# Blue_Pill_Clock.net
KiCad netlist of a schematic drawn in Altium Designer
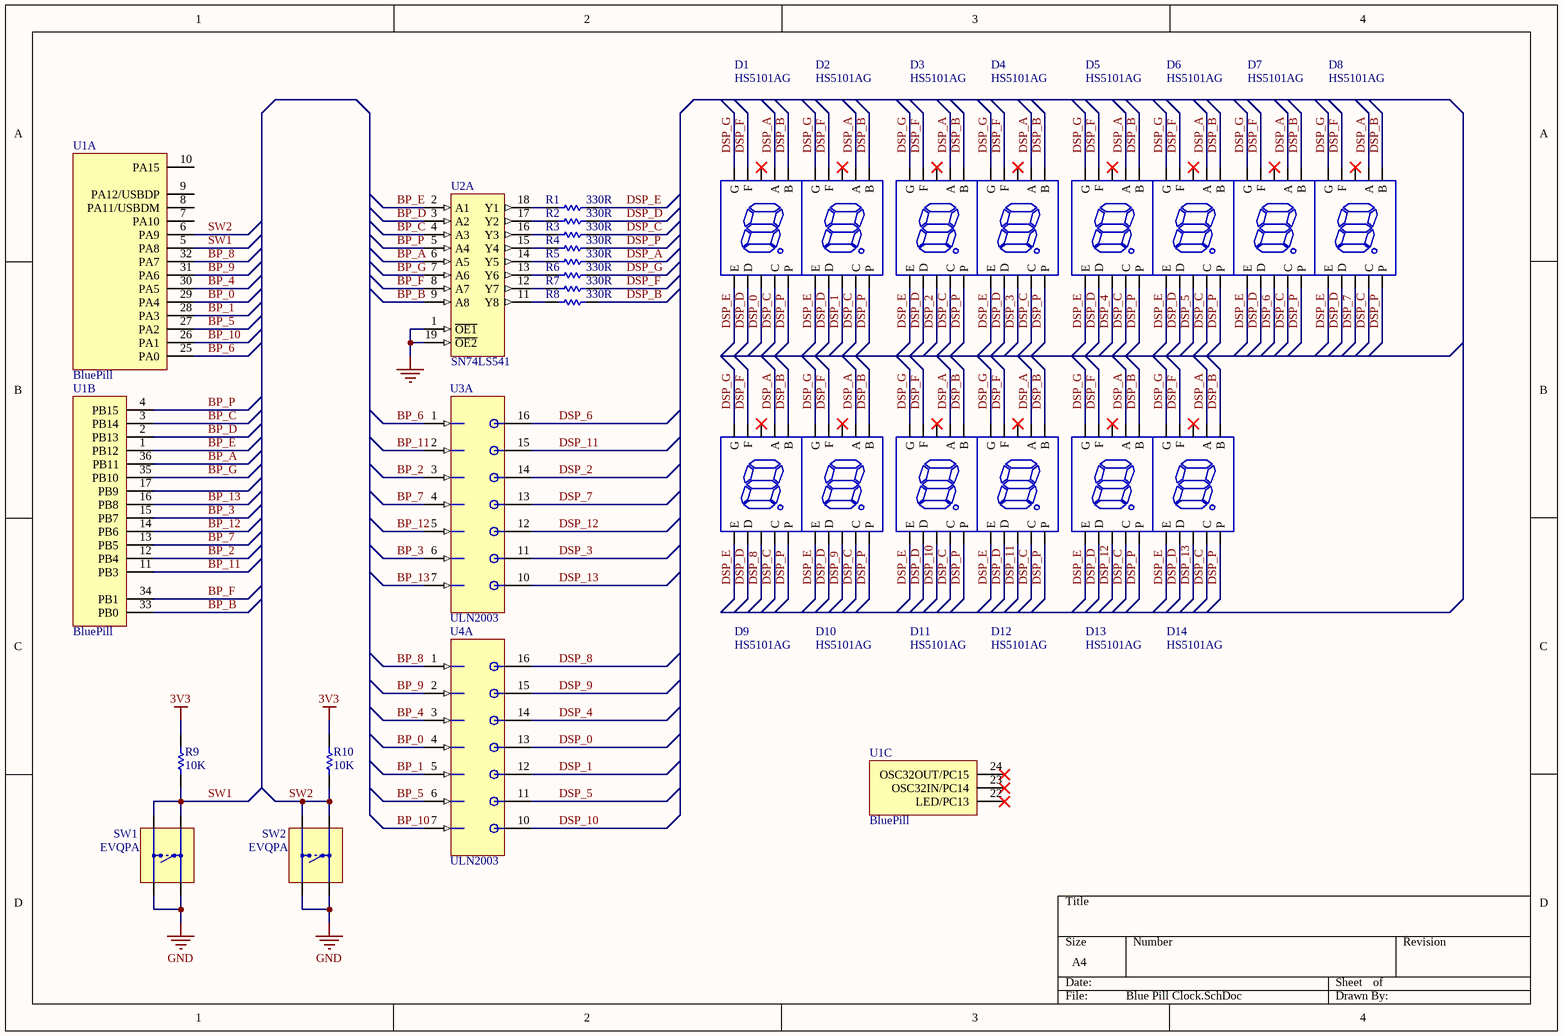
[diagram p0: Blue Pill Clock.SchDoc]

(export (version "E")
  (design (tool "Eeschema 10.0.6"))
  (components
    (comp (ref "D1")
      (value "HS5101AG")
      (footprint "HS5101AG")
      (description "Display 7-Segments Cathodo Common")
      (libsource (lib "Basic") (part "HS5101AG"))
    )
    (comp (ref "D2")
      (value "HS5101AG")
      (footprint "HS5101AG")
      (description "Display 7-Segments Cathodo Common")
      (libsource (lib "Basic") (part "HS5101AG"))
    )
    (comp (ref "D3")
      (value "HS5101AG")
      (footprint "HS5101AG")
      (description "Display 7-Segments Cathodo Common")
      (libsource (lib "Basic") (part "HS5101AG"))
    )
    (comp (ref "D4")
      (value "HS5101AG")
      (footprint "HS5101AG")
      (description "Display 7-Segments Cathodo Common")
      (libsource (lib "Basic") (part "HS5101AG"))
    )
    (comp (ref "D5")
      (value "HS5101AG")
      (footprint "HS5101AG")
      (description "Display 7-Segments Cathodo Common")
      (libsource (lib "Basic") (part "HS5101AG"))
    )
    (comp (ref "D6")
      (value "HS5101AG")
      (footprint "HS5101AG")
      (description "Display 7-Segments Cathodo Common")
      (libsource (lib "Basic") (part "HS5101AG"))
    )
    (comp (ref "D7")
      (value "HS5101AG")
      (footprint "HS5101AG")
      (description "Display 7-Segments Cathodo Common")
      (libsource (lib "Basic") (part "HS5101AG"))
    )
    (comp (ref "D8")
      (value "HS5101AG")
      (footprint "HS5101AG")
      (description "Display 7-Segments Cathodo Common")
      (libsource (lib "Basic") (part "HS5101AG"))
    )
    (comp (ref "D9")
      (value "HS5101AG")
      (footprint "HS5101AG")
      (description "Display 7-Segments Cathodo Common")
      (libsource (lib "Basic") (part "HS5101AG"))
    )
    (comp (ref "D10")
      (value "HS5101AG")
      (footprint "HS5101AG")
      (description "Display 7-Segments Cathodo Common")
      (libsource (lib "Basic") (part "HS5101AG"))
    )
    (comp (ref "D11")
      (value "HS5101AG")
      (footprint "HS5101AG")
      (description "Display 7-Segments Cathodo Common")
      (libsource (lib "Basic") (part "HS5101AG"))
    )
    (comp (ref "D12")
      (value "HS5101AG")
      (footprint "HS5101AG")
      (description "Display 7-Segments Cathodo Common")
      (libsource (lib "Basic") (part "HS5101AG"))
    )
    (comp (ref "D13")
      (value "HS5101AG")
      (footprint "HS5101AG")
      (description "Display 7-Segments Cathodo Common")
      (libsource (lib "Basic") (part "HS5101AG"))
    )
    (comp (ref "D14")
      (value "HS5101AG")
      (footprint "HS5101AG")
      (description "Display 7-Segments Cathodo Common")
      (libsource (lib "Basic") (part "HS5101AG"))
    )
    (comp (ref "R1")
      (value "330R")
      (footprint "0805")
      (description "Resistor")
      (libsource (lib "Basic") (part "Resistor"))
    )
    (comp (ref "R2")
      (value "330R")
      (footprint "0805")
      (description "Resistor")
      (libsource (lib "Basic") (part "Resistor"))
    )
    (comp (ref "R3")
      (value "330R")
      (footprint "0805")
      (description "Resistor")
      (libsource (lib "Basic") (part "Resistor"))
    )
    (comp (ref "R4")
      (value "330R")
      (footprint "0805")
      (description "Resistor")
      (libsource (lib "Basic") (part "Resistor"))
    )
    (comp (ref "R5")
      (value "330R")
      (footprint "0805")
      (description "Resistor")
      (libsource (lib "Basic") (part "Resistor"))
    )
    (comp (ref "R6")
      (value "330R")
      (footprint "0805")
      (description "Resistor")
      (libsource (lib "Basic") (part "Resistor"))
    )
    (comp (ref "R7")
      (value "330R")
      (footprint "0805")
      (description "Resistor")
      (libsource (lib "Basic") (part "Resistor"))
    )
    (comp (ref "R8")
      (value "330R")
      (footprint "0805")
      (description "Resistor")
      (libsource (lib "Basic") (part "Resistor"))
    )
    (comp (ref "R9")
      (value "10K")
      (footprint "0805")
      (description "Resistor")
      (libsource (lib "Basic") (part "Resistor"))
    )
    (comp (ref "R10")
      (value "10K")
      (footprint "0805")
      (description "Resistor")
      (libsource (lib "Basic") (part "Resistor"))
    )
    (comp (ref "SW1")
      (value "EVQPA")
      (footprint "EVQPAx09K")
      (description "5N Type Light Touch Switches")
      (libsource (lib "Panasonic") (part "EVQPA"))
    )
    (comp (ref "SW2")
      (value "EVQPA")
      (footprint "EVQPAx09K")
      (description "5N Type Light Touch Switches")
      (libsource (lib "Panasonic") (part "EVQPA"))
    )
    (comp (ref "U1")
      (value "BluePill")
      (footprint "Blue Pill")
      (description "STM32 Blue Pill")
      (libsource (lib "STM32 Blue Pill") (part "Blue Pill - Model 1"))
    )
    (comp (ref "U2")
      (value "SN74LS541")
      (footprint "PDIP20")
      (description "Octal Buffers and Line Drivers With 3-State Outputs")
      (libsource (lib "Texas Instruments") (part "SN74HC541 Type-2"))
    )
    (comp (ref "U3")
      (value "ULN2003")
      (footprint "PDIP16")
      (description "Seven Darlington arrays")
      (libsource (lib "ST Microelectronics") (part "UN200x - Model 1"))
    )
    (comp (ref "U4")
      (value "ULN2003")
      (footprint "PDIP16")
      (description "Seven Darlington arrays")
      (libsource (lib "ST Microelectronics") (part "UN200x - Model 1"))
    )
  )
  (nets
    (net (code "1") (name "/BP_0") (class "Default")
      (node (ref "U1") (pin "29") (pinfunction "PA4_29") (pintype "passive"))
      (node (ref "U4") (pin "4") (pinfunction "4_4") (pintype "input"))
    )
    (net (code "2") (name "/BP_1") (class "Default")
      (node (ref "U1") (pin "28") (pinfunction "PA3_28") (pintype "passive"))
      (node (ref "U4") (pin "5") (pinfunction "5_5") (pintype "input"))
    )
    (net (code "3") (name "/BP_2") (class "Default")
      (node (ref "U1") (pin "12") (pinfunction "PB4_12") (pintype "passive"))
      (node (ref "U3") (pin "3") (pinfunction "3_3") (pintype "input"))
    )
    (net (code "4") (name "/BP_3") (class "Default")
      (node (ref "U1") (pin "15") (pinfunction "PB7_15") (pintype "passive"))
      (node (ref "U3") (pin "6") (pinfunction "6_6") (pintype "input"))
    )
    (net (code "5") (name "/BP_4") (class "Default")
      (node (ref "U1") (pin "30") (pinfunction "PA5_30") (pintype "passive"))
      (node (ref "U4") (pin "3") (pinfunction "3_3") (pintype "input"))
    )
    (net (code "6") (name "/BP_5") (class "Default")
      (node (ref "U1") (pin "27") (pinfunction "PA2_27") (pintype "passive"))
      (node (ref "U4") (pin "6") (pinfunction "6_6") (pintype "input"))
    )
    (net (code "7") (name "/BP_6") (class "Default")
      (node (ref "U1") (pin "25") (pinfunction "PA0_25") (pintype "passive"))
      (node (ref "U3") (pin "1") (pinfunction "1_1") (pintype "input"))
    )
    (net (code "8") (name "/BP_7") (class "Default")
      (node (ref "U1") (pin "13") (pinfunction "PB5_13") (pintype "passive"))
      (node (ref "U3") (pin "4") (pinfunction "4_4") (pintype "input"))
    )
    (net (code "9") (name "/BP_8") (class "Default")
      (node (ref "U1") (pin "32") (pinfunction "PA7_32") (pintype "passive"))
      (node (ref "U4") (pin "1") (pinfunction "1_1") (pintype "input"))
    )
    (net (code "10") (name "/BP_9") (class "Default")
      (node (ref "U1") (pin "31") (pinfunction "PA6_31") (pintype "passive"))
      (node (ref "U4") (pin "2") (pinfunction "2_2") (pintype "input"))
    )
    (net (code "11") (name "/BP_10") (class "Default")
      (node (ref "U1") (pin "26") (pinfunction "PA1_26") (pintype "passive"))
      (node (ref "U4") (pin "7") (pinfunction "7_7") (pintype "input"))
    )
    (net (code "12") (name "/BP_11") (class "Default")
      (node (ref "U1") (pin "11") (pinfunction "PB3_11") (pintype "passive"))
      (node (ref "U3") (pin "2") (pinfunction "2_2") (pintype "input"))
    )
    (net (code "13") (name "/BP_12") (class "Default")
      (node (ref "U1") (pin "14") (pinfunction "PB6_14") (pintype "passive"))
      (node (ref "U3") (pin "5") (pinfunction "5_5") (pintype "input"))
    )
    (net (code "14") (name "/BP_13") (class "Default")
      (node (ref "U1") (pin "16") (pinfunction "PB8_16") (pintype "passive"))
      (node (ref "U3") (pin "7") (pinfunction "7_7") (pintype "input"))
    )
    (net (code "15") (name "/BP_A") (class "Default")
      (node (ref "U1") (pin "36") (pinfunction "PB11_36") (pintype "passive"))
      (node (ref "U2") (pin "6") (pinfunction "A5_6") (pintype "input"))
    )
    (net (code "16") (name "/BP_B") (class "Default")
      (node (ref "U1") (pin "33") (pinfunction "PB0_33") (pintype "passive"))
      (node (ref "U2") (pin "9") (pinfunction "A8_9") (pintype "input"))
    )
    (net (code "17") (name "/BP_C") (class "Default")
      (node (ref "U1") (pin "3") (pinfunction "PB14_3") (pintype "passive"))
      (node (ref "U2") (pin "4") (pinfunction "A3_4") (pintype "input"))
    )
    (net (code "18") (name "/BP_D") (class "Default")
      (node (ref "U1") (pin "2") (pinfunction "PB13_2") (pintype "passive"))
      (node (ref "U2") (pin "3") (pinfunction "A2_3") (pintype "input"))
    )
    (net (code "19") (name "/BP_E") (class "Default")
      (node (ref "U1") (pin "1") (pinfunction "PB12_1") (pintype "passive"))
      (node (ref "U2") (pin "2") (pinfunction "A1_2") (pintype "input"))
    )
    (net (code "20") (name "/BP_F") (class "Default")
      (node (ref "U1") (pin "34") (pinfunction "PB1_34") (pintype "passive"))
      (node (ref "U2") (pin "8") (pinfunction "A7_8") (pintype "input"))
    )
    (net (code "21") (name "/BP_G") (class "Default")
      (node (ref "U1") (pin "35") (pinfunction "PB10_35") (pintype "passive"))
      (node (ref "U2") (pin "7") (pinfunction "A6_7") (pintype "input"))
    )
    (net (code "22") (name "/BP_P") (class "Default")
      (node (ref "U1") (pin "4") (pinfunction "PB15_4") (pintype "passive"))
      (node (ref "U2") (pin "5") (pinfunction "A4_5") (pintype "input"))
    )
    (net (code "23") (name "/DSP_0") (class "Default")
      (node (ref "D1") (pin "3") (pinfunction "GND2_3") (pintype "power_in"))
      (node (ref "U4") (pin "13") (pinfunction "13_13") (pintype "open_collector"))
    )
    (net (code "24") (name "/DSP_1") (class "Default")
      (node (ref "D2") (pin "3") (pinfunction "GND2_3") (pintype "power_in"))
      (node (ref "U4") (pin "12") (pinfunction "12_12") (pintype "open_collector"))
    )
    (net (code "25") (name "/DSP_2") (class "Default")
      (node (ref "D3") (pin "3") (pinfunction "GND2_3") (pintype "power_in"))
      (node (ref "U3") (pin "14") (pinfunction "14_14") (pintype "open_collector"))
    )
    (net (code "26") (name "/DSP_3") (class "Default")
      (node (ref "D4") (pin "3") (pinfunction "GND2_3") (pintype "power_in"))
      (node (ref "U3") (pin "11") (pinfunction "11_11") (pintype "open_collector"))
    )
    (net (code "27") (name "/DSP_4") (class "Default")
      (node (ref "D5") (pin "3") (pinfunction "GND2_3") (pintype "power_in"))
      (node (ref "U4") (pin "14") (pinfunction "14_14") (pintype "open_collector"))
    )
    (net (code "28") (name "/DSP_5") (class "Default")
      (node (ref "D6") (pin "3") (pinfunction "GND2_3") (pintype "power_in"))
      (node (ref "U4") (pin "11") (pinfunction "11_11") (pintype "open_collector"))
    )
    (net (code "29") (name "/DSP_6") (class "Default")
      (node (ref "D7") (pin "3") (pinfunction "GND2_3") (pintype "power_in"))
      (node (ref "U3") (pin "16") (pinfunction "16_16") (pintype "open_collector"))
    )
    (net (code "30") (name "/DSP_7") (class "Default")
      (node (ref "D8") (pin "3") (pinfunction "GND2_3") (pintype "power_in"))
      (node (ref "U3") (pin "13") (pinfunction "13_13") (pintype "open_collector"))
    )
    (net (code "31") (name "/DSP_8") (class "Default")
      (node (ref "D9") (pin "3") (pinfunction "GND2_3") (pintype "power_in"))
      (node (ref "U4") (pin "16") (pinfunction "16_16") (pintype "open_collector"))
    )
    (net (code "32") (name "/DSP_9") (class "Default")
      (node (ref "D10") (pin "3") (pinfunction "GND2_3") (pintype "power_in"))
      (node (ref "U4") (pin "15") (pinfunction "15_15") (pintype "open_collector"))
    )
    (net (code "33") (name "/DSP_10") (class "Default")
      (node (ref "D11") (pin "3") (pinfunction "GND2_3") (pintype "power_in"))
      (node (ref "U4") (pin "10") (pinfunction "10_10") (pintype "open_collector"))
    )
    (net (code "34") (name "/DSP_11") (class "Default")
      (node (ref "D12") (pin "3") (pinfunction "GND2_3") (pintype "power_in"))
      (node (ref "U3") (pin "15") (pinfunction "15_15") (pintype "open_collector"))
    )
    (net (code "35") (name "/DSP_12") (class "Default")
      (node (ref "D13") (pin "3") (pinfunction "GND2_3") (pintype "power_in"))
      (node (ref "U3") (pin "12") (pinfunction "12_12") (pintype "open_collector"))
    )
    (net (code "36") (name "/DSP_13") (class "Default")
      (node (ref "D14") (pin "3") (pinfunction "GND2_3") (pintype "power_in"))
      (node (ref "U3") (pin "10") (pinfunction "10_10") (pintype "open_collector"))
    )
    (net (code "37") (name "/DSP_A") (class "Default")
      (node (ref "D1") (pin "7") (pinfunction "A_7") (pintype "passive"))
      (node (ref "D10") (pin "7") (pinfunction "A_7") (pintype "passive"))
      (node (ref "D11") (pin "7") (pinfunction "A_7") (pintype "passive"))
      (node (ref "D12") (pin "7") (pinfunction "A_7") (pintype "passive"))
      (node (ref "D13") (pin "7") (pinfunction "A_7") (pintype "passive"))
      (node (ref "D14") (pin "7") (pinfunction "A_7") (pintype "passive"))
      (node (ref "D2") (pin "7") (pinfunction "A_7") (pintype "passive"))
      (node (ref "D3") (pin "7") (pinfunction "A_7") (pintype "passive"))
      (node (ref "D4") (pin "7") (pinfunction "A_7") (pintype "passive"))
      (node (ref "D5") (pin "7") (pinfunction "A_7") (pintype "passive"))
      (node (ref "D6") (pin "7") (pinfunction "A_7") (pintype "passive"))
      (node (ref "D7") (pin "7") (pinfunction "A_7") (pintype "passive"))
      (node (ref "D8") (pin "7") (pinfunction "A_7") (pintype "passive"))
      (node (ref "D9") (pin "7") (pinfunction "A_7") (pintype "passive"))
      (node (ref "R5") (pin "2") (pinfunction "2_2") (pintype "passive"))
    )
    (net (code "38") (name "/DSP_B") (class "Default")
      (node (ref "D1") (pin "6") (pinfunction "B_6") (pintype "passive"))
      (node (ref "D10") (pin "6") (pinfunction "B_6") (pintype "passive"))
      (node (ref "D11") (pin "6") (pinfunction "B_6") (pintype "passive"))
      (node (ref "D12") (pin "6") (pinfunction "B_6") (pintype "passive"))
      (node (ref "D13") (pin "6") (pinfunction "B_6") (pintype "passive"))
      (node (ref "D14") (pin "6") (pinfunction "B_6") (pintype "passive"))
      (node (ref "D2") (pin "6") (pinfunction "B_6") (pintype "passive"))
      (node (ref "D3") (pin "6") (pinfunction "B_6") (pintype "passive"))
      (node (ref "D4") (pin "6") (pinfunction "B_6") (pintype "passive"))
      (node (ref "D5") (pin "6") (pinfunction "B_6") (pintype "passive"))
      (node (ref "D6") (pin "6") (pinfunction "B_6") (pintype "passive"))
      (node (ref "D7") (pin "6") (pinfunction "B_6") (pintype "passive"))
      (node (ref "D8") (pin "6") (pinfunction "B_6") (pintype "passive"))
      (node (ref "D9") (pin "6") (pinfunction "B_6") (pintype "passive"))
      (node (ref "R8") (pin "2") (pinfunction "2_2") (pintype "passive"))
    )
    (net (code "39") (name "/DSP_C") (class "Default")
      (node (ref "D1") (pin "4") (pinfunction "C_4") (pintype "passive"))
      (node (ref "D10") (pin "4") (pinfunction "C_4") (pintype "passive"))
      (node (ref "D11") (pin "4") (pinfunction "C_4") (pintype "passive"))
      (node (ref "D12") (pin "4") (pinfunction "C_4") (pintype "passive"))
      (node (ref "D13") (pin "4") (pinfunction "C_4") (pintype "passive"))
      (node (ref "D14") (pin "4") (pinfunction "C_4") (pintype "passive"))
      (node (ref "D2") (pin "4") (pinfunction "C_4") (pintype "passive"))
      (node (ref "D3") (pin "4") (pinfunction "C_4") (pintype "passive"))
      (node (ref "D4") (pin "4") (pinfunction "C_4") (pintype "passive"))
      (node (ref "D5") (pin "4") (pinfunction "C_4") (pintype "passive"))
      (node (ref "D6") (pin "4") (pinfunction "C_4") (pintype "passive"))
      (node (ref "D7") (pin "4") (pinfunction "C_4") (pintype "passive"))
      (node (ref "D8") (pin "4") (pinfunction "C_4") (pintype "passive"))
      (node (ref "D9") (pin "4") (pinfunction "C_4") (pintype "passive"))
      (node (ref "R3") (pin "2") (pinfunction "2_2") (pintype "passive"))
    )
    (net (code "40") (name "/DSP_D") (class "Default")
      (node (ref "D1") (pin "2") (pinfunction "D_2") (pintype "passive"))
      (node (ref "D10") (pin "2") (pinfunction "D_2") (pintype "passive"))
      (node (ref "D11") (pin "2") (pinfunction "D_2") (pintype "passive"))
      (node (ref "D12") (pin "2") (pinfunction "D_2") (pintype "passive"))
      (node (ref "D13") (pin "2") (pinfunction "D_2") (pintype "passive"))
      (node (ref "D14") (pin "2") (pinfunction "D_2") (pintype "passive"))
      (node (ref "D2") (pin "2") (pinfunction "D_2") (pintype "passive"))
      (node (ref "D3") (pin "2") (pinfunction "D_2") (pintype "passive"))
      (node (ref "D4") (pin "2") (pinfunction "D_2") (pintype "passive"))
      (node (ref "D5") (pin "2") (pinfunction "D_2") (pintype "passive"))
      (node (ref "D6") (pin "2") (pinfunction "D_2") (pintype "passive"))
      (node (ref "D7") (pin "2") (pinfunction "D_2") (pintype "passive"))
      (node (ref "D8") (pin "2") (pinfunction "D_2") (pintype "passive"))
      (node (ref "D9") (pin "2") (pinfunction "D_2") (pintype "passive"))
      (node (ref "R2") (pin "2") (pinfunction "2_2") (pintype "passive"))
    )
    (net (code "41") (name "/DSP_E") (class "Default")
      (node (ref "D1") (pin "1") (pinfunction "E_1") (pintype "passive"))
      (node (ref "D10") (pin "1") (pinfunction "E_1") (pintype "passive"))
      (node (ref "D11") (pin "1") (pinfunction "E_1") (pintype "passive"))
      (node (ref "D12") (pin "1") (pinfunction "E_1") (pintype "passive"))
      (node (ref "D13") (pin "1") (pinfunction "E_1") (pintype "passive"))
      (node (ref "D14") (pin "1") (pinfunction "E_1") (pintype "passive"))
      (node (ref "D2") (pin "1") (pinfunction "E_1") (pintype "passive"))
      (node (ref "D3") (pin "1") (pinfunction "E_1") (pintype "passive"))
      (node (ref "D4") (pin "1") (pinfunction "E_1") (pintype "passive"))
      (node (ref "D5") (pin "1") (pinfunction "E_1") (pintype "passive"))
      (node (ref "D6") (pin "1") (pinfunction "E_1") (pintype "passive"))
      (node (ref "D7") (pin "1") (pinfunction "E_1") (pintype "passive"))
      (node (ref "D8") (pin "1") (pinfunction "E_1") (pintype "passive"))
      (node (ref "D9") (pin "1") (pinfunction "E_1") (pintype "passive"))
      (node (ref "R1") (pin "2") (pinfunction "2_2") (pintype "passive"))
    )
    (net (code "42") (name "/DSP_F") (class "Default")
      (node (ref "D1") (pin "9") (pinfunction "F_9") (pintype "passive"))
      (node (ref "D10") (pin "9") (pinfunction "F_9") (pintype "passive"))
      (node (ref "D11") (pin "9") (pinfunction "F_9") (pintype "passive"))
      (node (ref "D12") (pin "9") (pinfunction "F_9") (pintype "passive"))
      (node (ref "D13") (pin "9") (pinfunction "F_9") (pintype "passive"))
      (node (ref "D14") (pin "9") (pinfunction "F_9") (pintype "passive"))
      (node (ref "D2") (pin "9") (pinfunction "F_9") (pintype "passive"))
      (node (ref "D3") (pin "9") (pinfunction "F_9") (pintype "passive"))
      (node (ref "D4") (pin "9") (pinfunction "F_9") (pintype "passive"))
      (node (ref "D5") (pin "9") (pinfunction "F_9") (pintype "passive"))
      (node (ref "D6") (pin "9") (pinfunction "F_9") (pintype "passive"))
      (node (ref "D7") (pin "9") (pinfunction "F_9") (pintype "passive"))
      (node (ref "D8") (pin "9") (pinfunction "F_9") (pintype "passive"))
      (node (ref "D9") (pin "9") (pinfunction "F_9") (pintype "passive"))
      (node (ref "R7") (pin "2") (pinfunction "2_2") (pintype "passive"))
    )
    (net (code "43") (name "/DSP_G") (class "Default")
      (node (ref "D1") (pin "10") (pinfunction "G_10") (pintype "passive"))
      (node (ref "D10") (pin "10") (pinfunction "G_10") (pintype "passive"))
      (node (ref "D11") (pin "10") (pinfunction "G_10") (pintype "passive"))
      (node (ref "D12") (pin "10") (pinfunction "G_10") (pintype "passive"))
      (node (ref "D13") (pin "10") (pinfunction "G_10") (pintype "passive"))
      (node (ref "D14") (pin "10") (pinfunction "G_10") (pintype "passive"))
      (node (ref "D2") (pin "10") (pinfunction "G_10") (pintype "passive"))
      (node (ref "D3") (pin "10") (pinfunction "G_10") (pintype "passive"))
      (node (ref "D4") (pin "10") (pinfunction "G_10") (pintype "passive"))
      (node (ref "D5") (pin "10") (pinfunction "G_10") (pintype "passive"))
      (node (ref "D6") (pin "10") (pinfunction "G_10") (pintype "passive"))
      (node (ref "D7") (pin "10") (pinfunction "G_10") (pintype "passive"))
      (node (ref "D8") (pin "10") (pinfunction "G_10") (pintype "passive"))
      (node (ref "D9") (pin "10") (pinfunction "G_10") (pintype "passive"))
      (node (ref "R6") (pin "2") (pinfunction "2_2") (pintype "passive"))
    )
    (net (code "44") (name "/DSP_P") (class "Default")
      (node (ref "D1") (pin "5") (pinfunction "P_5") (pintype "passive"))
      (node (ref "D10") (pin "5") (pinfunction "P_5") (pintype "passive"))
      (node (ref "D11") (pin "5") (pinfunction "P_5") (pintype "passive"))
      (node (ref "D12") (pin "5") (pinfunction "P_5") (pintype "passive"))
      (node (ref "D13") (pin "5") (pinfunction "P_5") (pintype "passive"))
      (node (ref "D14") (pin "5") (pinfunction "P_5") (pintype "passive"))
      (node (ref "D2") (pin "5") (pinfunction "P_5") (pintype "passive"))
      (node (ref "D3") (pin "5") (pinfunction "P_5") (pintype "passive"))
      (node (ref "D4") (pin "5") (pinfunction "P_5") (pintype "passive"))
      (node (ref "D5") (pin "5") (pinfunction "P_5") (pintype "passive"))
      (node (ref "D6") (pin "5") (pinfunction "P_5") (pintype "passive"))
      (node (ref "D7") (pin "5") (pinfunction "P_5") (pintype "passive"))
      (node (ref "D8") (pin "5") (pinfunction "P_5") (pintype "passive"))
      (node (ref "D9") (pin "5") (pinfunction "P_5") (pintype "passive"))
      (node (ref "R4") (pin "2") (pinfunction "2_2") (pintype "passive"))
    )
    (net (code "45") (name "/SW1") (class "Default")
      (node (ref "R9") (pin "1") (pinfunction "1_1") (pintype "passive"))
      (node (ref "SW1") (pin "3") (pinfunction "3_3") (pintype "power_in"))
      (node (ref "SW1") (pin "4") (pinfunction "4_4") (pintype "power_in"))
      (node (ref "U1") (pin "5") (pinfunction "PA8_5") (pintype "passive"))
    )
    (net (code "46") (name "/SW2") (class "Default")
      (node (ref "R10") (pin "1") (pinfunction "1_1") (pintype "passive"))
      (node (ref "SW2") (pin "3") (pinfunction "3_3") (pintype "power_in"))
      (node (ref "SW2") (pin "4") (pinfunction "4_4") (pintype "power_in"))
      (node (ref "U1") (pin "6") (pinfunction "PA9_6") (pintype "passive"))
    )
    (net (code "47") (name "3V3") (class "Default")
      (node (ref "R10") (pin "2") (pinfunction "2_2") (pintype "passive"))
      (node (ref "R9") (pin "2") (pinfunction "2_2") (pintype "passive"))
    )
    (net (code "48") (name "GND") (class "Default")
      (node (ref "SW1") (pin "1") (pinfunction "1_1") (pintype "power_in"))
      (node (ref "SW1") (pin "2") (pinfunction "2_2") (pintype "power_in"))
      (node (ref "SW2") (pin "1") (pinfunction "1_1") (pintype "power_in"))
      (node (ref "SW2") (pin "2") (pinfunction "2_2") (pintype "power_in"))
      (node (ref "U2") (pin "1") (pinfunction "~{OE1}_1") (pintype "input"))
      (node (ref "U2") (pin "19") (pinfunction "~{OE2}_19") (pintype "input"))
    )
    (net (code "49") (name "Net-(U2A-Y1)") (class "Default")
      (node (ref "R1") (pin "1") (pinfunction "1_1") (pintype "passive"))
      (node (ref "U2") (pin "18") (pinfunction "Y1_18") (pintype "output"))
    )
    (net (code "50") (name "Net-(U2A-Y2)") (class "Default")
      (node (ref "R2") (pin "1") (pinfunction "1_1") (pintype "passive"))
      (node (ref "U2") (pin "17") (pinfunction "Y2_17") (pintype "output"))
    )
    (net (code "51") (name "Net-(U2A-Y3)") (class "Default")
      (node (ref "R3") (pin "1") (pinfunction "1_1") (pintype "passive"))
      (node (ref "U2") (pin "16") (pinfunction "Y3_16") (pintype "output"))
    )
    (net (code "52") (name "Net-(U2A-Y4)") (class "Default")
      (node (ref "R4") (pin "1") (pinfunction "1_1") (pintype "passive"))
      (node (ref "U2") (pin "15") (pinfunction "Y4_15") (pintype "output"))
    )
    (net (code "53") (name "Net-(U2A-Y5)") (class "Default")
      (node (ref "R5") (pin "1") (pinfunction "1_1") (pintype "passive"))
      (node (ref "U2") (pin "14") (pinfunction "Y5_14") (pintype "output"))
    )
    (net (code "54") (name "Net-(U2A-Y6)") (class "Default")
      (node (ref "R6") (pin "1") (pinfunction "1_1") (pintype "passive"))
      (node (ref "U2") (pin "13") (pinfunction "Y6_13") (pintype "output"))
    )
    (net (code "55") (name "Net-(U2A-Y7)") (class "Default")
      (node (ref "R7") (pin "1") (pinfunction "1_1") (pintype "passive"))
      (node (ref "U2") (pin "12") (pinfunction "Y7_12") (pintype "output"))
    )
    (net (code "56") (name "Net-(U2A-Y8)") (class "Default")
      (node (ref "R8") (pin "1") (pinfunction "1_1") (pintype "passive"))
      (node (ref "U2") (pin "11") (pinfunction "Y8_11") (pintype "output"))
    )
    (net (code "57") (name "unconnected-(D1-GND1-Pad8)") (class "Default")
      (node (ref "D1") (pin "8") (pinfunction "GND1_8") (pintype "power_in+no_connect"))
    )
    (net (code "58") (name "unconnected-(D2-GND1-Pad8)") (class "Default")
      (node (ref "D2") (pin "8") (pinfunction "GND1_8") (pintype "power_in+no_connect"))
    )
    (net (code "59") (name "unconnected-(D3-GND1-Pad8)") (class "Default")
      (node (ref "D3") (pin "8") (pinfunction "GND1_8") (pintype "power_in+no_connect"))
    )
    (net (code "60") (name "unconnected-(D4-GND1-Pad8)") (class "Default")
      (node (ref "D4") (pin "8") (pinfunction "GND1_8") (pintype "power_in+no_connect"))
    )
    (net (code "61") (name "unconnected-(D5-GND1-Pad8)") (class "Default")
      (node (ref "D5") (pin "8") (pinfunction "GND1_8") (pintype "power_in+no_connect"))
    )
    (net (code "62") (name "unconnected-(D6-GND1-Pad8)") (class "Default")
      (node (ref "D6") (pin "8") (pinfunction "GND1_8") (pintype "power_in+no_connect"))
    )
    (net (code "63") (name "unconnected-(D7-GND1-Pad8)") (class "Default")
      (node (ref "D7") (pin "8") (pinfunction "GND1_8") (pintype "power_in+no_connect"))
    )
    (net (code "64") (name "unconnected-(D8-GND1-Pad8)") (class "Default")
      (node (ref "D8") (pin "8") (pinfunction "GND1_8") (pintype "power_in+no_connect"))
    )
    (net (code "65") (name "unconnected-(D9-GND1-Pad8)") (class "Default")
      (node (ref "D9") (pin "8") (pinfunction "GND1_8") (pintype "power_in+no_connect"))
    )
    (net (code "66") (name "unconnected-(D10-GND1-Pad8)") (class "Default")
      (node (ref "D10") (pin "8") (pinfunction "GND1_8") (pintype "power_in+no_connect"))
    )
    (net (code "67") (name "unconnected-(D11-GND1-Pad8)") (class "Default")
      (node (ref "D11") (pin "8") (pinfunction "GND1_8") (pintype "power_in+no_connect"))
    )
    (net (code "68") (name "unconnected-(D12-GND1-Pad8)") (class "Default")
      (node (ref "D12") (pin "8") (pinfunction "GND1_8") (pintype "power_in+no_connect"))
    )
    (net (code "69") (name "unconnected-(D13-GND1-Pad8)") (class "Default")
      (node (ref "D13") (pin "8") (pinfunction "GND1_8") (pintype "power_in+no_connect"))
    )
    (net (code "70") (name "unconnected-(D14-GND1-Pad8)") (class "Default")
      (node (ref "D14") (pin "8") (pinfunction "GND1_8") (pintype "power_in+no_connect"))
    )
    (net (code "71") (name "unconnected-(U1A-PA10-Pad7)") (class "Default")
      (node (ref "U1") (pin "7") (pinfunction "PA10_7") (pintype "passive"))
    )
    (net (code "72") (name "unconnected-(U1A-PA11{slash}USBDM-Pad8)") (class "Default")
      (node (ref "U1") (pin "8") (pinfunction "PA11/USBDM_8") (pintype "passive"))
    )
    (net (code "73") (name "unconnected-(U1A-PA12{slash}USBDP-Pad9)") (class "Default")
      (node (ref "U1") (pin "9") (pinfunction "PA12/USBDP_9") (pintype "passive"))
    )
    (net (code "74") (name "unconnected-(U1A-PA15-Pad10)") (class "Default")
      (node (ref "U1") (pin "10") (pinfunction "PA15_10") (pintype "passive"))
    )
    (net (code "75") (name "unconnected-(U1B-PB9-Pad17)") (class "Default")
      (node (ref "U1") (pin "17") (pinfunction "PB9_17") (pintype "passive"))
    )
    (net (code "76") (name "unconnected-(U1C-LED{slash}PC13-Pad22)") (class "Default")
      (node (ref "U1") (pin "22") (pinfunction "LED/PC13_22") (pintype "passive+no_connect"))
    )
    (net (code "77") (name "unconnected-(U1C-OSC32IN{slash}PC14-Pad23)") (class "Default")
      (node (ref "U1") (pin "23") (pinfunction "OSC32IN/PC14_23") (pintype "passive+no_connect"))
    )
    (net (code "78") (name "unconnected-(U1C-OSC32OUT{slash}PC15-Pad24)") (class "Default")
      (node (ref "U1") (pin "24") (pinfunction "OSC32OUT/PC15_24") (pintype "passive+no_connect"))
    )
  )
)
